# StepperSynth2_3_Interface.net
KiCad netlist of a schematic drawn in EAGLE
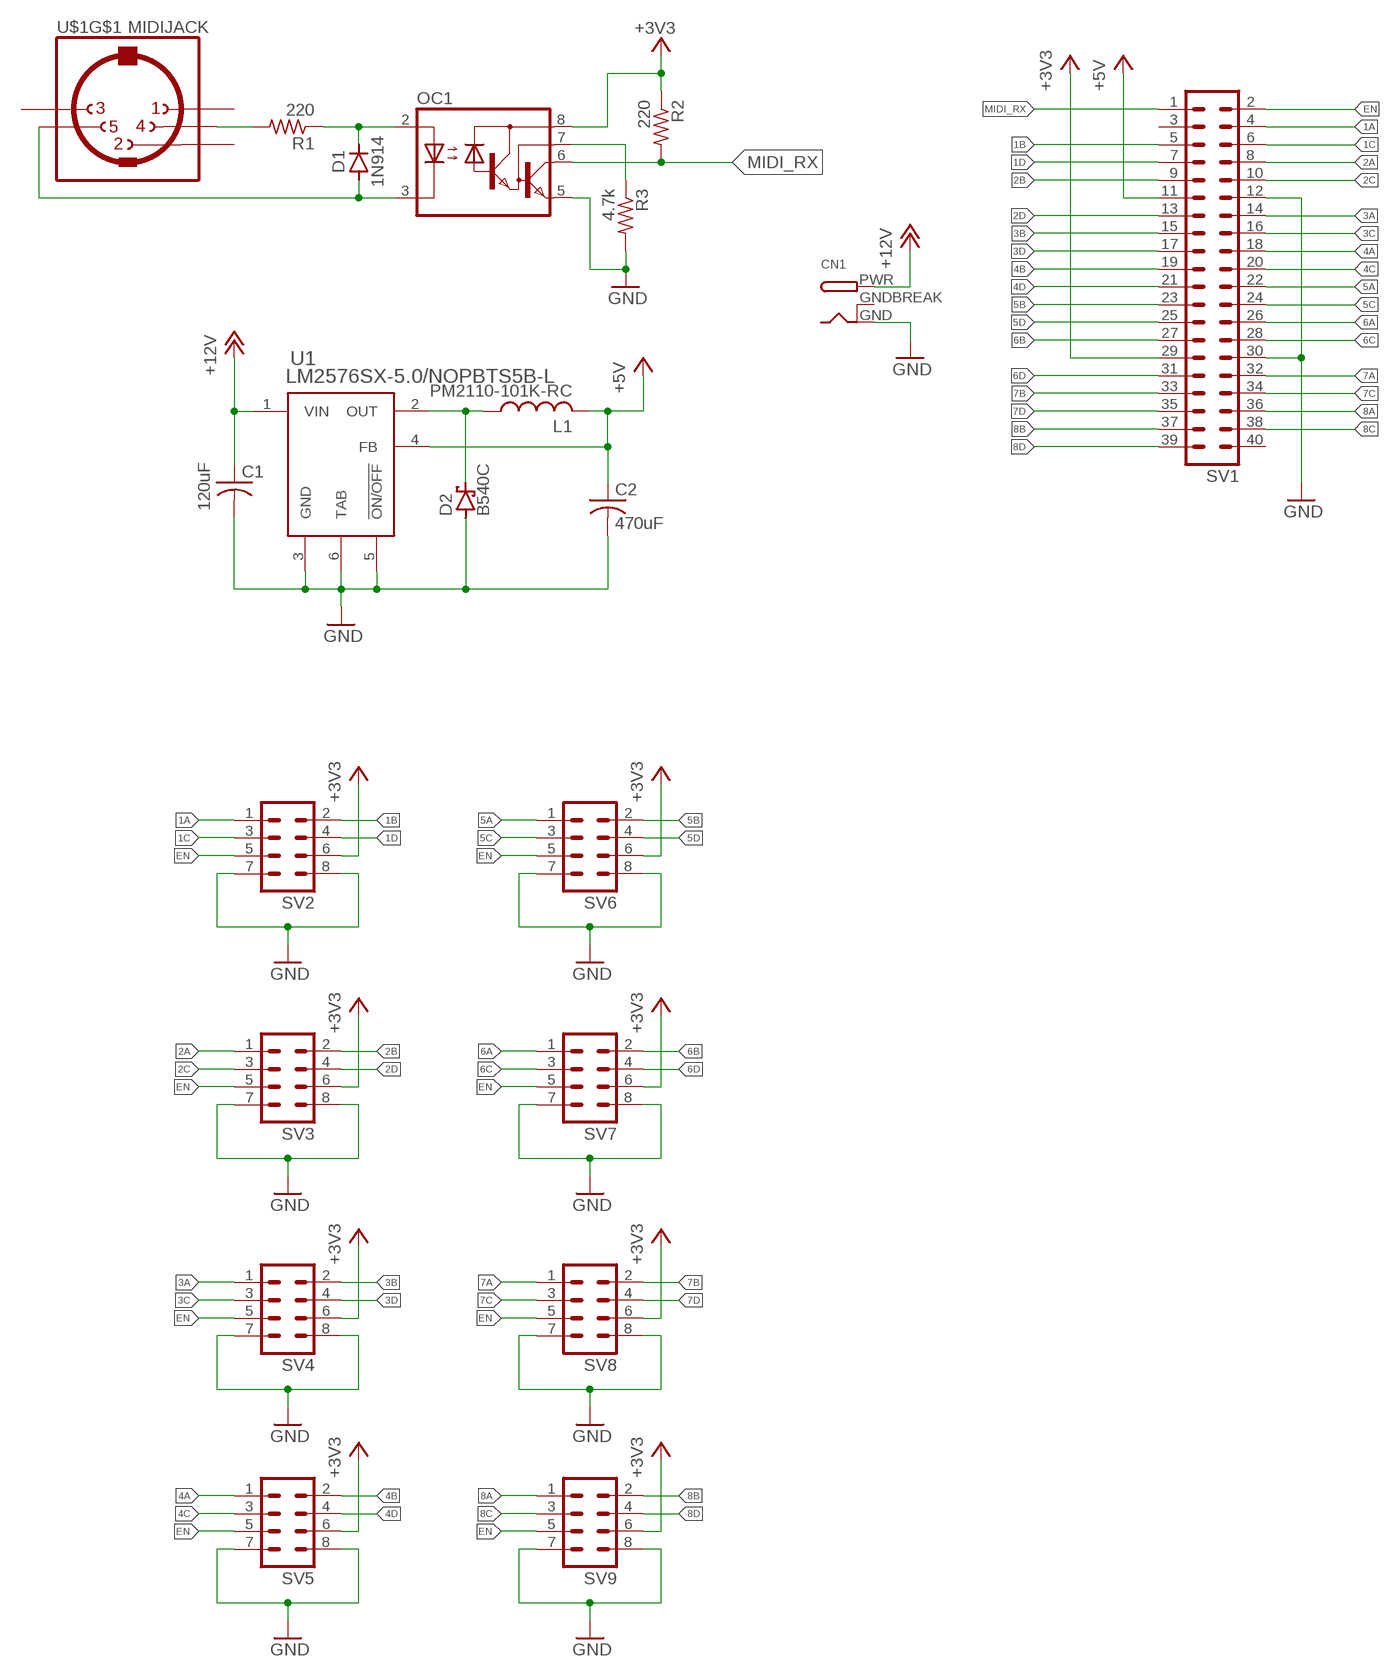
[diagram p0: schematic, sheet 1]

(export (version "E")
  (design (tool "Eeschema 10.0.6"))
  (components
    (comp (ref "C1")
      (value "120uF")
      (footprint "eagle-import:PCAP_SVP_C6-L")
      (fields (field (name "MANUFACTURER_PART_NUMBER") "20SVPF120M"))
      (libsource (lib "eagle-import") (part "20SVPF120MPCAP_SVP_C6-L"))
    )
    (comp (ref "C2")
      (value "470uF")
      (footprint "eagle-import:U2-P-L")
      (fields (field (name "MANUFACTURER_PART_NUMBER") "UUD1A471MNL1GS"))
      (libsource (lib "eagle-import") (part "UUD1A471MNL1GSU2-P-L"))
    )
    (comp (ref "CN1")
      (value "DCBARRELPTH")
      (footprint "eagle-import:DCJACK_2MM_PTH")
      (libsource (lib "eagle-import") (part "DCBARRELPTH"))
    )
    (comp (ref "D1")
      (value "1N914")
      (footprint "eagle-import:DO35-7")
      (libsource (lib "eagle-import") (part "1N914"))
    )
    (comp (ref "D2")
      (value "B540C")
      (footprint "eagle-import:SMC")
      (libsource (lib "eagle-import") (part "SCHOTTKY-DIODESMC"))
    )
    (comp (ref "L1")
      (value "PM2110-101K-RC")
      (footprint "eagle-import:IND_PM2110")
      (fields (field (name "MANUFACTURER_PART_NUMBER") "PM2110101KRC"))
      (libsource (lib "eagle-import") (part "PM2110-101K-RC"))
    )
    (comp (ref "OC1")
      (value "6N138")
      (footprint "eagle-import:DIL08")
      (libsource (lib "eagle-import") (part "6N138"))
    )
    (comp (ref "R1")
      (value "220")
      (footprint "eagle-import:0204_5")
      (libsource (lib "eagle-import") (part "R-US_0204/5"))
    )
    (comp (ref "R2")
      (value "220")
      (footprint "eagle-import:0204_5")
      (libsource (lib "eagle-import") (part "R-US_0204/5"))
    )
    (comp (ref "R3")
      (value "4.7k")
      (footprint "eagle-import:0204_5")
      (libsource (lib "eagle-import") (part "R-US_0204/5"))
    )
    (comp (ref "SV1")
      (value "MA20-2")
      (footprint "eagle-import:MA20-2")
      (libsource (lib "eagle-import") (part "MA20-2"))
    )
    (comp (ref "SV2")
      (value "MA04-2")
      (footprint "eagle-import:MA04-2")
      (libsource (lib "eagle-import") (part "MA04-2"))
    )
    (comp (ref "SV3")
      (value "MA04-2")
      (footprint "eagle-import:MA04-2")
      (libsource (lib "eagle-import") (part "MA04-2"))
    )
    (comp (ref "SV4")
      (value "MA04-2")
      (footprint "eagle-import:MA04-2")
      (libsource (lib "eagle-import") (part "MA04-2"))
    )
    (comp (ref "SV5")
      (value "MA04-2")
      (footprint "eagle-import:MA04-2")
      (libsource (lib "eagle-import") (part "MA04-2"))
    )
    (comp (ref "SV6")
      (value "MA04-2")
      (footprint "eagle-import:MA04-2")
      (libsource (lib "eagle-import") (part "MA04-2"))
    )
    (comp (ref "SV7")
      (value "MA04-2")
      (footprint "eagle-import:MA04-2")
      (libsource (lib "eagle-import") (part "MA04-2"))
    )
    (comp (ref "SV8")
      (value "MA04-2")
      (footprint "eagle-import:MA04-2")
      (libsource (lib "eagle-import") (part "MA04-2"))
    )
    (comp (ref "SV9")
      (value "MA04-2")
      (footprint "eagle-import:MA04-2")
      (libsource (lib "eagle-import") (part "MA04-2"))
    )
    (comp (ref "U$1")
      (value "MIDIJACK")
      (footprint "eagle-import:CP-2350")
      (libsource (lib "eagle-import") (part "MIDIJACK"))
    )
    (comp (ref "U1")
      (value "LM2576SX-5.0/NOPBTS5B-L")
      (footprint "eagle-import:TS5B-L")
      (fields (field (name "MANUFACTURER_PART_NUMBER") "LM2576SX5.0NOPB"))
      (libsource (lib "eagle-import") (part "LM2576SX-5.0/NOPBTS5B-L"))
    )
  )
  (nets
    (net (code "1") (name "+3V3") (class "Default")
      (node (ref "OC1") (pin "8") (pinfunction "VCC_8") (pintype "passive"))
      (node (ref "R2") (pin "1") (pinfunction "1_1") (pintype "passive"))
      (node (ref "SV1") (pin "29") (pinfunction "29_29") (pintype "passive"))
      (node (ref "SV2") (pin "6") (pinfunction "6_6") (pintype "passive"))
      (node (ref "SV3") (pin "6") (pinfunction "6_6") (pintype "passive"))
      (node (ref "SV4") (pin "6") (pinfunction "6_6") (pintype "passive"))
      (node (ref "SV5") (pin "6") (pinfunction "6_6") (pintype "passive"))
      (node (ref "SV6") (pin "6") (pinfunction "6_6") (pintype "passive"))
      (node (ref "SV7") (pin "6") (pinfunction "6_6") (pintype "passive"))
      (node (ref "SV8") (pin "6") (pinfunction "6_6") (pintype "passive"))
      (node (ref "SV9") (pin "6") (pinfunction "6_6") (pintype "passive"))
    )
    (net (code "2") (name "+5V") (class "Default")
      (node (ref "C2") (pin "1") (pinfunction "+_1") (pintype "passive"))
      (node (ref "L1") (pin "2") (pinfunction "2_2") (pintype "passive"))
      (node (ref "SV1") (pin "11") (pinfunction "11_11") (pintype "passive"))
      (node (ref "U1") (pin "4") (pinfunction "FB_4") (pintype "input"))
    )
    (net (code "3") (name "+12V") (class "Default")
      (node (ref "C1") (pin "1") (pinfunction "+_1") (pintype "passive"))
      (node (ref "CN1") (pin "PWR") (pinfunction "PWR_PWR") (pintype "power_in"))
      (node (ref "U1") (pin "1") (pinfunction "VIN_1") (pintype "power_in"))
    )
    (net (code "4") (name "/GNDBREAK") (class "Default")
      (node (ref "CN1") (pin "GNDBREAK") (pinfunction "GNDBREAK_GNDBREAK") (pintype "power_in"))
    )
    (net (code "5") (name "1A") (class "Default")
      (node (ref "SV1") (pin "4") (pinfunction "4_4") (pintype "passive"))
      (node (ref "SV2") (pin "1") (pinfunction "1_1") (pintype "passive"))
    )
    (net (code "6") (name "1B") (class "Default")
      (node (ref "SV1") (pin "5") (pinfunction "5_5") (pintype "passive"))
      (node (ref "SV2") (pin "2") (pinfunction "2_2") (pintype "passive"))
    )
    (net (code "7") (name "1C") (class "Default")
      (node (ref "SV1") (pin "6") (pinfunction "6_6") (pintype "passive"))
      (node (ref "SV2") (pin "3") (pinfunction "3_3") (pintype "passive"))
    )
    (net (code "8") (name "1D") (class "Default")
      (node (ref "SV1") (pin "7") (pinfunction "7_7") (pintype "passive"))
      (node (ref "SV2") (pin "4") (pinfunction "4_4") (pintype "passive"))
    )
    (net (code "9") (name "2A") (class "Default")
      (node (ref "SV1") (pin "8") (pinfunction "8_8") (pintype "passive"))
      (node (ref "SV3") (pin "1") (pinfunction "1_1") (pintype "passive"))
    )
    (net (code "10") (name "2B") (class "Default")
      (node (ref "SV1") (pin "9") (pinfunction "9_9") (pintype "passive"))
      (node (ref "SV3") (pin "2") (pinfunction "2_2") (pintype "passive"))
    )
    (net (code "11") (name "2C") (class "Default")
      (node (ref "SV1") (pin "10") (pinfunction "10_10") (pintype "passive"))
      (node (ref "SV3") (pin "3") (pinfunction "3_3") (pintype "passive"))
    )
    (net (code "12") (name "2D") (class "Default")
      (node (ref "SV1") (pin "13") (pinfunction "13_13") (pintype "passive"))
      (node (ref "SV3") (pin "4") (pinfunction "4_4") (pintype "passive"))
    )
    (net (code "13") (name "3A") (class "Default")
      (node (ref "SV1") (pin "14") (pinfunction "14_14") (pintype "passive"))
      (node (ref "SV4") (pin "1") (pinfunction "1_1") (pintype "passive"))
    )
    (net (code "14") (name "3B") (class "Default")
      (node (ref "SV1") (pin "15") (pinfunction "15_15") (pintype "passive"))
      (node (ref "SV4") (pin "2") (pinfunction "2_2") (pintype "passive"))
    )
    (net (code "15") (name "3C") (class "Default")
      (node (ref "SV1") (pin "16") (pinfunction "16_16") (pintype "passive"))
      (node (ref "SV4") (pin "3") (pinfunction "3_3") (pintype "passive"))
    )
    (net (code "16") (name "3D") (class "Default")
      (node (ref "SV1") (pin "17") (pinfunction "17_17") (pintype "passive"))
      (node (ref "SV4") (pin "4") (pinfunction "4_4") (pintype "passive"))
    )
    (net (code "17") (name "4A") (class "Default")
      (node (ref "SV1") (pin "18") (pinfunction "18_18") (pintype "passive"))
      (node (ref "SV5") (pin "1") (pinfunction "1_1") (pintype "passive"))
    )
    (net (code "18") (name "4B") (class "Default")
      (node (ref "SV1") (pin "19") (pinfunction "19_19") (pintype "passive"))
      (node (ref "SV5") (pin "2") (pinfunction "2_2") (pintype "passive"))
    )
    (net (code "19") (name "4C") (class "Default")
      (node (ref "SV1") (pin "20") (pinfunction "20_20") (pintype "passive"))
      (node (ref "SV5") (pin "3") (pinfunction "3_3") (pintype "passive"))
    )
    (net (code "20") (name "4D") (class "Default")
      (node (ref "SV1") (pin "21") (pinfunction "21_21") (pintype "passive"))
      (node (ref "SV5") (pin "4") (pinfunction "4_4") (pintype "passive"))
    )
    (net (code "21") (name "5A") (class "Default")
      (node (ref "SV1") (pin "22") (pinfunction "22_22") (pintype "passive"))
      (node (ref "SV6") (pin "1") (pinfunction "1_1") (pintype "passive"))
    )
    (net (code "22") (name "5B") (class "Default")
      (node (ref "SV1") (pin "23") (pinfunction "23_23") (pintype "passive"))
      (node (ref "SV6") (pin "2") (pinfunction "2_2") (pintype "passive"))
    )
    (net (code "23") (name "5C") (class "Default")
      (node (ref "SV1") (pin "24") (pinfunction "24_24") (pintype "passive"))
      (node (ref "SV6") (pin "3") (pinfunction "3_3") (pintype "passive"))
    )
    (net (code "24") (name "5D") (class "Default")
      (node (ref "SV1") (pin "25") (pinfunction "25_25") (pintype "passive"))
      (node (ref "SV6") (pin "4") (pinfunction "4_4") (pintype "passive"))
    )
    (net (code "25") (name "6A") (class "Default")
      (node (ref "SV1") (pin "26") (pinfunction "26_26") (pintype "passive"))
      (node (ref "SV7") (pin "1") (pinfunction "1_1") (pintype "passive"))
    )
    (net (code "26") (name "6B") (class "Default")
      (node (ref "SV1") (pin "27") (pinfunction "27_27") (pintype "passive"))
      (node (ref "SV7") (pin "2") (pinfunction "2_2") (pintype "passive"))
    )
    (net (code "27") (name "6C") (class "Default")
      (node (ref "SV1") (pin "28") (pinfunction "28_28") (pintype "passive"))
      (node (ref "SV7") (pin "3") (pinfunction "3_3") (pintype "passive"))
    )
    (net (code "28") (name "6D") (class "Default")
      (node (ref "SV1") (pin "31") (pinfunction "31_31") (pintype "passive"))
      (node (ref "SV7") (pin "4") (pinfunction "4_4") (pintype "passive"))
    )
    (net (code "29") (name "7A") (class "Default")
      (node (ref "SV1") (pin "32") (pinfunction "32_32") (pintype "passive"))
      (node (ref "SV8") (pin "1") (pinfunction "1_1") (pintype "passive"))
    )
    (net (code "30") (name "7B") (class "Default")
      (node (ref "SV1") (pin "33") (pinfunction "33_33") (pintype "passive"))
      (node (ref "SV8") (pin "2") (pinfunction "2_2") (pintype "passive"))
    )
    (net (code "31") (name "7C") (class "Default")
      (node (ref "SV1") (pin "34") (pinfunction "34_34") (pintype "passive"))
      (node (ref "SV8") (pin "3") (pinfunction "3_3") (pintype "passive"))
    )
    (net (code "32") (name "7D") (class "Default")
      (node (ref "SV1") (pin "35") (pinfunction "35_35") (pintype "passive"))
      (node (ref "SV8") (pin "4") (pinfunction "4_4") (pintype "passive"))
    )
    (net (code "33") (name "8A") (class "Default")
      (node (ref "SV1") (pin "36") (pinfunction "36_36") (pintype "passive"))
      (node (ref "SV9") (pin "1") (pinfunction "1_1") (pintype "passive"))
    )
    (net (code "34") (name "8B") (class "Default")
      (node (ref "SV1") (pin "37") (pinfunction "37_37") (pintype "passive"))
      (node (ref "SV9") (pin "2") (pinfunction "2_2") (pintype "passive"))
    )
    (net (code "35") (name "8C") (class "Default")
      (node (ref "SV1") (pin "38") (pinfunction "38_38") (pintype "passive"))
      (node (ref "SV9") (pin "3") (pinfunction "3_3") (pintype "passive"))
    )
    (net (code "36") (name "8D") (class "Default")
      (node (ref "SV1") (pin "39") (pinfunction "39_39") (pintype "passive"))
      (node (ref "SV9") (pin "4") (pinfunction "4_4") (pintype "passive"))
    )
    (net (code "37") (name "EN") (class "Default")
      (node (ref "SV1") (pin "2") (pinfunction "2_2") (pintype "passive"))
      (node (ref "SV2") (pin "5") (pinfunction "5_5") (pintype "passive"))
      (node (ref "SV3") (pin "5") (pinfunction "5_5") (pintype "passive"))
      (node (ref "SV4") (pin "5") (pinfunction "5_5") (pintype "passive"))
      (node (ref "SV5") (pin "5") (pinfunction "5_5") (pintype "passive"))
      (node (ref "SV6") (pin "5") (pinfunction "5_5") (pintype "passive"))
      (node (ref "SV7") (pin "5") (pinfunction "5_5") (pintype "passive"))
      (node (ref "SV8") (pin "5") (pinfunction "5_5") (pintype "passive"))
      (node (ref "SV9") (pin "5") (pinfunction "5_5") (pintype "passive"))
    )
    (net (code "38") (name "GND") (class "Default")
      (node (ref "C1") (pin "2") (pinfunction "-_2") (pintype "passive"))
      (node (ref "C2") (pin "2") (pinfunction "-_2") (pintype "passive"))
      (node (ref "CN1") (pin "GND") (pinfunction "GND_GND") (pintype "power_in"))
      (node (ref "D2") (pin "A") (pinfunction "A_A") (pintype "passive"))
      (node (ref "OC1") (pin "5") (pinfunction "GND_5") (pintype "passive"))
      (node (ref "R3") (pin "2") (pinfunction "2_2") (pintype "passive"))
      (node (ref "SV1") (pin "12") (pinfunction "12_12") (pintype "passive"))
      (node (ref "SV1") (pin "30") (pinfunction "30_30") (pintype "passive"))
      (node (ref "SV2") (pin "7") (pinfunction "7_7") (pintype "passive"))
      (node (ref "SV2") (pin "8") (pinfunction "8_8") (pintype "passive"))
      (node (ref "SV3") (pin "7") (pinfunction "7_7") (pintype "passive"))
      (node (ref "SV3") (pin "8") (pinfunction "8_8") (pintype "passive"))
      (node (ref "SV4") (pin "7") (pinfunction "7_7") (pintype "passive"))
      (node (ref "SV4") (pin "8") (pinfunction "8_8") (pintype "passive"))
      (node (ref "SV5") (pin "7") (pinfunction "7_7") (pintype "passive"))
      (node (ref "SV5") (pin "8") (pinfunction "8_8") (pintype "passive"))
      (node (ref "SV6") (pin "7") (pinfunction "7_7") (pintype "passive"))
      (node (ref "SV6") (pin "8") (pinfunction "8_8") (pintype "passive"))
      (node (ref "SV7") (pin "7") (pinfunction "7_7") (pintype "passive"))
      (node (ref "SV7") (pin "8") (pinfunction "8_8") (pintype "passive"))
      (node (ref "SV8") (pin "7") (pinfunction "7_7") (pintype "passive"))
      (node (ref "SV8") (pin "8") (pinfunction "8_8") (pintype "passive"))
      (node (ref "SV9") (pin "7") (pinfunction "7_7") (pintype "passive"))
      (node (ref "SV9") (pin "8") (pinfunction "8_8") (pintype "passive"))
      (node (ref "U1") (pin "3") (pinfunction "GND_3") (pintype "power_in"))
      (node (ref "U1") (pin "5") (pinfunction "~{ON/OFF}_5") (pintype "input"))
      (node (ref "U1") (pin "6") (pinfunction "TAB_6") (pintype "power_in"))
    )
    (net (code "39") (name "MIDI_RX") (class "Default")
      (node (ref "OC1") (pin "6") (pinfunction "VO_6") (pintype "passive"))
      (node (ref "R2") (pin "2") (pinfunction "2_2") (pintype "passive"))
      (node (ref "SV1") (pin "1") (pinfunction "1_1") (pintype "passive"))
    )
    (net (code "40") (name "Net-(OC1-A)") (class "Default")
      (node (ref "D1") (pin "C") (pinfunction "C_C") (pintype "passive"))
      (node (ref "OC1") (pin "2") (pinfunction "A_2") (pintype "passive"))
      (node (ref "R1") (pin "1") (pinfunction "1_1") (pintype "passive"))
    )
    (net (code "41") (name "Net-(OC1-C)") (class "Default")
      (node (ref "D1") (pin "A") (pinfunction "A_A") (pintype "passive"))
      (node (ref "OC1") (pin "3") (pinfunction "C_3") (pintype "passive"))
      (node (ref "U$1") (pin "5") (pinfunction "5_5") (pintype "passive"))
    )
    (net (code "42") (name "Net-(OC1-VB)") (class "Default")
      (node (ref "OC1") (pin "7") (pinfunction "VB_7") (pintype "passive"))
      (node (ref "R3") (pin "1") (pinfunction "1_1") (pintype "passive"))
    )
    (net (code "43") (name "Net-(R1-Pad2)") (class "Default")
      (node (ref "R1") (pin "2") (pinfunction "2_2") (pintype "passive"))
      (node (ref "U$1") (pin "4") (pinfunction "4_4") (pintype "passive"))
    )
    (net (code "44") (name "Net-(U1-OUT)") (class "Default")
      (node (ref "D2") (pin "C") (pinfunction "C_C") (pintype "passive"))
      (node (ref "L1") (pin "1") (pinfunction "1_1") (pintype "passive"))
      (node (ref "U1") (pin "2") (pinfunction "OUT_2") (pintype "power_in"))
    )
    (net (code "45") (name "unconnected-(SV1-Pad3)") (class "Default")
      (node (ref "SV1") (pin "3") (pinfunction "3_3") (pintype "passive"))
    )
    (net (code "46") (name "unconnected-(SV1-Pad40)") (class "Default")
      (node (ref "SV1") (pin "40") (pinfunction "40_40") (pintype "passive"))
    )
    (net (code "47") (name "unconnected-(U$1-Pad1)") (class "Default")
      (node (ref "U$1") (pin "1") (pinfunction "1_1") (pintype "passive"))
    )
    (net (code "48") (name "unconnected-(U$1-Pad2)") (class "Default")
      (node (ref "U$1") (pin "2") (pinfunction "2_2") (pintype "passive"))
    )
    (net (code "49") (name "unconnected-(U$1-Pad3)") (class "Default")
      (node (ref "U$1") (pin "3") (pinfunction "3_3") (pintype "passive"))
    )
  )
)
